# stoichea_v0_1.net
KiCad netlist of a schematic drawn in EAGLE
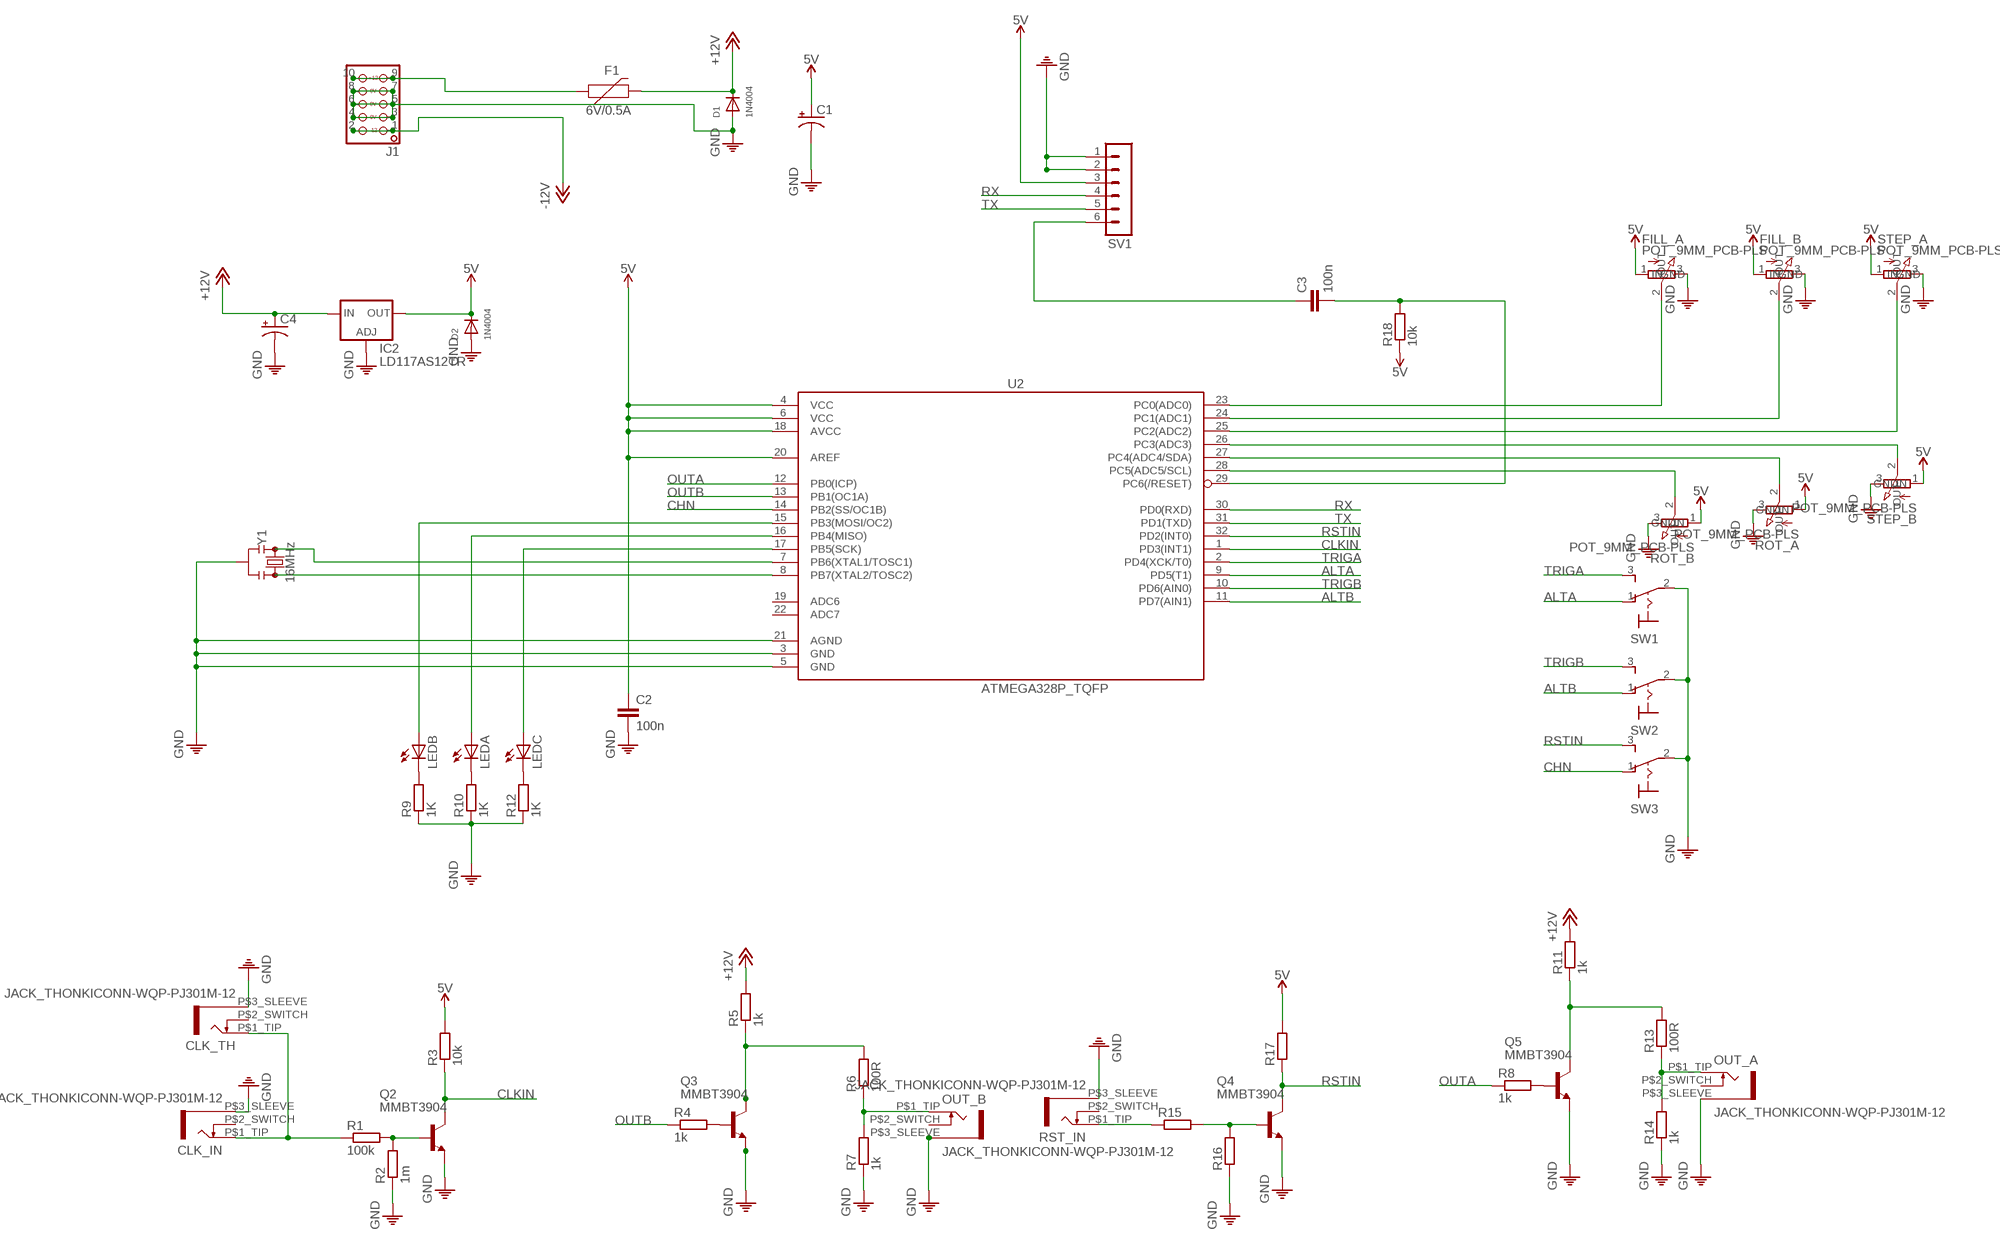
[diagram p0: schematic, sheet 1]

(export (version "E")
  (design (tool "Eeschema 10.0.6"))
  (components
    (comp (ref "C1")
      (value "CAPACITOR_POLARIZED-USE2.5-5")
      (footprint "eagle-import:E2,5-5")
      (libsource (lib "eagle-import") (part "CAPACITOR_POLARIZED-USE2.5-5"))
    )
    (comp (ref "C2")
      (value "100n")
      (footprint "eagle-import:C0603K")
      (libsource (lib "eagle-import") (part "CAPACITOR-EUC0603K"))
    )
    (comp (ref "C3")
      (value "100n")
      (footprint "eagle-import:C0603K")
      (libsource (lib "eagle-import") (part "CAPACITOR-EUC0603K"))
    )
    (comp (ref "C4")
      (value "CAPACITOR_POLARIZED-USE2.5-5")
      (footprint "eagle-import:E2,5-5")
      (libsource (lib "eagle-import") (part "CAPACITOR_POLARIZED-USE2.5-5"))
    )
    (comp (ref "CLK_IN")
      (value "JACK_THONKICONN-WQP-PJ301M-12")
      (footprint "eagle-import:WQP-PJ301M-12_JACK")
      (libsource (lib "eagle-import") (part "JACK_THONKICONN-WQP-PJ301M-12"))
    )
    (comp (ref "CLK_TH")
      (value "JACK_THONKICONN-WQP-PJ301M-12")
      (footprint "eagle-import:WQP-PJ301M-12_JACK")
      (libsource (lib "eagle-import") (part "JACK_THONKICONN-WQP-PJ301M-12"))
    )
    (comp (ref "D1")
      (value "1N4004")
      (footprint "eagle-import:SOD-323F")
      (libsource (lib "eagle-import") (part "DIODESOD-323F"))
    )
    (comp (ref "D2")
      (value "1N4004")
      (footprint "eagle-import:SOD-323F")
      (libsource (lib "eagle-import") (part "DIODESOD-323F"))
    )
    (comp (ref "F1")
      (value "6V/0.5A")
      (footprint "eagle-import:1206")
      (libsource (lib "eagle-import") (part "FUSE-PPTC_HALF-AMP"))
    )
    (comp (ref "FILL_A")
      (value "POT_9MM_PCB-PLS")
      (footprint "eagle-import:9MM_PLS")
      (libsource (lib "eagle-import") (part "POT_9MM_PCB-PLS"))
    )
    (comp (ref "FILL_B")
      (value "POT_9MM_PCB-PLS")
      (footprint "eagle-import:9MM_PLS")
      (libsource (lib "eagle-import") (part "POT_9MM_PCB-PLS"))
    )
    (comp (ref "IC2")
      (value "LD117AS12TR")
      (footprint "eagle-import:SOT223")
      (libsource (lib "eagle-import") (part "LD117A?S12TR"))
    )
    (comp (ref "J1")
      (value "HEADER-EUROPWR_2X05-OPEN")
      (footprint "eagle-import:2X05_EUROPWR_OPEN")
      (libsource (lib "eagle-import") (part "HEADER-EUROPWR_2X05-OPEN"))
    )
    (comp (ref "LEDA")
      (value "LED3MM")
      (footprint "eagle-import:LED3MM")
      (libsource (lib "eagle-import") (part "LED3MM"))
    )
    (comp (ref "LEDB")
      (value "LED3MM")
      (footprint "eagle-import:LED3MM")
      (libsource (lib "eagle-import") (part "LED3MM"))
    )
    (comp (ref "LEDC")
      (value "LED3MM")
      (footprint "eagle-import:LED3MM")
      (libsource (lib "eagle-import") (part "LED3MM"))
    )
    (comp (ref "OUT_A")
      (value "JACK_THONKICONN-WQP-PJ301M-12")
      (footprint "eagle-import:WQP-PJ301M-12_JACK")
      (libsource (lib "eagle-import") (part "JACK_THONKICONN-WQP-PJ301M-12"))
    )
    (comp (ref "OUT_B")
      (value "JACK_THONKICONN-WQP-PJ301M-12")
      (footprint "eagle-import:WQP-PJ301M-12_JACK")
      (libsource (lib "eagle-import") (part "JACK_THONKICONN-WQP-PJ301M-12"))
    )
    (comp (ref "Q2")
      (value "MMBT3904")
      (footprint "eagle-import:SOT23-BEC")
      (libsource (lib "eagle-import") (part "TRANSISTOR-NPN-SOT23-BECMMBT3904LT1"))
    )
    (comp (ref "Q3")
      (value "MMBT3904")
      (footprint "eagle-import:SOT23-BEC")
      (libsource (lib "eagle-import") (part "TRANSISTOR-NPN-SOT23-BECMMBT3904LT1"))
    )
    (comp (ref "Q4")
      (value "MMBT3904")
      (footprint "eagle-import:SOT23-BEC")
      (libsource (lib "eagle-import") (part "TRANSISTOR-NPN-SOT23-BECMMBT3904LT1"))
    )
    (comp (ref "Q5")
      (value "MMBT3904")
      (footprint "eagle-import:SOT23-BEC")
      (libsource (lib "eagle-import") (part "TRANSISTOR-NPN-SOT23-BECMMBT3904LT1"))
    )
    (comp (ref "R1")
      (value "100k")
      (footprint "eagle-import:R0603")
      (libsource (lib "eagle-import") (part "RESISTOR-EU_R0603"))
    )
    (comp (ref "R2")
      (value "1m")
      (footprint "eagle-import:R0603")
      (libsource (lib "eagle-import") (part "RESISTOR-EU_R0603"))
    )
    (comp (ref "R3")
      (value "10k")
      (footprint "eagle-import:R0603")
      (libsource (lib "eagle-import") (part "RESISTOR-EU_R0603"))
    )
    (comp (ref "R4")
      (value "1k")
      (footprint "eagle-import:R0603")
      (libsource (lib "eagle-import") (part "RESISTOR-EU_R0603"))
    )
    (comp (ref "R5")
      (value "1k")
      (footprint "eagle-import:R0603")
      (libsource (lib "eagle-import") (part "RESISTOR-EU_R0603"))
    )
    (comp (ref "R6")
      (value "100R")
      (footprint "eagle-import:R0603")
      (libsource (lib "eagle-import") (part "RESISTOR-EU_R0603"))
    )
    (comp (ref "R7")
      (value "1k")
      (footprint "eagle-import:R0603")
      (libsource (lib "eagle-import") (part "RESISTOR-EU_R0603"))
    )
    (comp (ref "R8")
      (value "1k")
      (footprint "eagle-import:R0603")
      (libsource (lib "eagle-import") (part "RESISTOR-EU_R0603"))
    )
    (comp (ref "R9")
      (value "1K")
      (footprint "eagle-import:R0603")
      (libsource (lib "eagle-import") (part "RESISTOR-EU_R0603"))
    )
    (comp (ref "R10")
      (value "1K")
      (footprint "eagle-import:R0603")
      (libsource (lib "eagle-import") (part "RESISTOR-EU_R0603"))
    )
    (comp (ref "R11")
      (value "1k")
      (footprint "eagle-import:R0603")
      (libsource (lib "eagle-import") (part "RESISTOR-EU_R0603"))
    )
    (comp (ref "R12")
      (value "1K")
      (footprint "eagle-import:R0603")
      (libsource (lib "eagle-import") (part "RESISTOR-EU_R0603"))
    )
    (comp (ref "R13")
      (value "100R")
      (footprint "eagle-import:R0603")
      (libsource (lib "eagle-import") (part "RESISTOR-EU_R0603"))
    )
    (comp (ref "R14")
      (value "1k")
      (footprint "eagle-import:R0603")
      (libsource (lib "eagle-import") (part "RESISTOR-EU_R0603"))
    )
    (comp (ref "R15")
      (value "RESISTOR-EU_R0603")
      (footprint "eagle-import:R0603")
      (libsource (lib "eagle-import") (part "RESISTOR-EU_R0603"))
    )
    (comp (ref "R16")
      (value "RESISTOR-EU_R0603")
      (footprint "eagle-import:R0603")
      (libsource (lib "eagle-import") (part "RESISTOR-EU_R0603"))
    )
    (comp (ref "R17")
      (value "RESISTOR-EU_R0603")
      (footprint "eagle-import:R0603")
      (libsource (lib "eagle-import") (part "RESISTOR-EU_R0603"))
    )
    (comp (ref "R18")
      (value "10k")
      (footprint "eagle-import:R0603")
      (libsource (lib "eagle-import") (part "RESISTOR-EU_R0603"))
    )
    (comp (ref "ROT_A")
      (value "POT_9MM_PCB-PLS")
      (footprint "eagle-import:9MM_PLS")
      (libsource (lib "eagle-import") (part "POT_9MM_PCB-PLS"))
    )
    (comp (ref "ROT_B")
      (value "POT_9MM_PCB-PLS")
      (footprint "eagle-import:9MM_PLS")
      (libsource (lib "eagle-import") (part "POT_9MM_PCB-PLS"))
    )
    (comp (ref "RST_IN")
      (value "JACK_THONKICONN-WQP-PJ301M-12")
      (footprint "eagle-import:WQP-PJ301M-12_JACK")
      (libsource (lib "eagle-import") (part "JACK_THONKICONN-WQP-PJ301M-12"))
    )
    (comp (ref "STEP_A")
      (value "POT_9MM_PCB-PLS")
      (footprint "eagle-import:9MM_PLS")
      (libsource (lib "eagle-import") (part "POT_9MM_PCB-PLS"))
    )
    (comp (ref "STEP_B")
      (value "POT_9MM_PCB-PLS")
      (footprint "eagle-import:9MM_PLS")
      (libsource (lib "eagle-import") (part "POT_9MM_PCB-PLS"))
    )
    (comp (ref "SV1")
      (value "MA06-1")
      (footprint "eagle-import:MA06-1")
      (libsource (lib "eagle-import") (part "MA06-1"))
    )
    (comp (ref "SW1")
      (value "SWITCH-SPDT-320-916")
      (footprint "eagle-import:320-916")
      (libsource (lib "eagle-import") (part "SWITCH-SPDT-320-916"))
    )
    (comp (ref "SW2")
      (value "SWITCH-SPDT-320-916")
      (footprint "eagle-import:320-916")
      (libsource (lib "eagle-import") (part "SWITCH-SPDT-320-916"))
    )
    (comp (ref "SW3")
      (value "SWITCH-SPDT-320-916")
      (footprint "eagle-import:320-916")
      (libsource (lib "eagle-import") (part "SWITCH-SPDT-320-916"))
    )
    (comp (ref "U2")
      (value "ATMEGA328P_TQFP")
      (footprint "eagle-import:TQFP32-08")
      (libsource (lib "eagle-import") (part "ATMEGA328P_TQFP"))
    )
    (comp (ref "Y1")
      (value "16MHz")
      (footprint "eagle-import:RESONATOR-SMD-3.2X1.3")
      (libsource (lib "eagle-import") (part "RESONATORSMD-3.2X1.3"))
    )
  )
  (nets
    (net (code "1") (name "+12V") (class "Default")
      (node (ref "C4") (pin "+") (pinfunction "+_+") (pintype "passive"))
      (node (ref "D1") (pin "C") (pinfunction "C_C") (pintype "passive"))
      (node (ref "F1") (pin "2") (pinfunction "2_2") (pintype "bidirectional"))
      (node (ref "IC2") (pin "3") (pinfunction "IN_3") (pintype "input"))
      (node (ref "R11") (pin "2") (pinfunction "2_2") (pintype "passive"))
      (node (ref "R5") (pin "2") (pinfunction "2_2") (pintype "passive"))
    )
    (net (code "2") (name "-12V") (class "Default")
      (node (ref "J1") (pin "1") (pinfunction "1_1") (pintype "passive"))
      (node (ref "J1") (pin "2") (pinfunction "2_2") (pintype "passive"))
    )
    (net (code "3") (name "/ALTA") (class "Default")
      (node (ref "SW1") (pin "1") (pinfunction "O_1") (pintype "passive"))
      (node (ref "U2") (pin "9") (pinfunction "PD5(T1)_9") (pintype "bidirectional"))
    )
    (net (code "4") (name "/ALTB") (class "Default")
      (node (ref "SW2") (pin "1") (pinfunction "O_1") (pintype "passive"))
      (node (ref "U2") (pin "11") (pinfunction "PD7(AIN1)_11") (pintype "bidirectional"))
    )
    (net (code "5") (name "/CHN") (class "Default")
      (node (ref "SW3") (pin "1") (pinfunction "O_1") (pintype "passive"))
      (node (ref "U2") (pin "14") (pinfunction "PB2(SS/OC1B)_14") (pintype "bidirectional"))
    )
    (net (code "6") (name "/CLKIN") (class "Default")
      (node (ref "Q2") (pin "C") (pinfunction "C_C") (pintype "passive"))
      (node (ref "R3") (pin "1") (pinfunction "1_1") (pintype "passive"))
      (node (ref "U2") (pin "1") (pinfunction "PD3(INT1)_1") (pintype "bidirectional"))
    )
    (net (code "7") (name "/OUTA") (class "Default")
      (node (ref "R8") (pin "1") (pinfunction "1_1") (pintype "passive"))
      (node (ref "U2") (pin "12") (pinfunction "PB0(ICP)_12") (pintype "bidirectional"))
    )
    (net (code "8") (name "/OUTB") (class "Default")
      (node (ref "R4") (pin "1") (pinfunction "1_1") (pintype "passive"))
      (node (ref "U2") (pin "13") (pinfunction "PB1(OC1A)_13") (pintype "bidirectional"))
    )
    (net (code "9") (name "/RSTIN") (class "Default")
      (node (ref "Q4") (pin "C") (pinfunction "C_C") (pintype "passive"))
      (node (ref "R17") (pin "1") (pinfunction "1_1") (pintype "passive"))
      (node (ref "SW3") (pin "3") (pinfunction "S_3") (pintype "passive"))
      (node (ref "U2") (pin "32") (pinfunction "PD2(INT0)_32") (pintype "bidirectional"))
    )
    (net (code "10") (name "/RX") (class "Default")
      (node (ref "SV1") (pin "4") (pinfunction "4_4") (pintype "passive"))
      (node (ref "U2") (pin "30") (pinfunction "PD0(RXD)_30") (pintype "bidirectional"))
    )
    (net (code "11") (name "/TRIGA") (class "Default")
      (node (ref "SW1") (pin "3") (pinfunction "S_3") (pintype "passive"))
      (node (ref "U2") (pin "2") (pinfunction "PD4(XCK/T0)_2") (pintype "bidirectional"))
    )
    (net (code "12") (name "/TRIGB") (class "Default")
      (node (ref "SW2") (pin "3") (pinfunction "S_3") (pintype "passive"))
      (node (ref "U2") (pin "10") (pinfunction "PD6(AIN0)_10") (pintype "bidirectional"))
    )
    (net (code "13") (name "/TX") (class "Default")
      (node (ref "SV1") (pin "5") (pinfunction "5_5") (pintype "passive"))
      (node (ref "U2") (pin "31") (pinfunction "PD1(TXD)_31") (pintype "bidirectional"))
    )
    (net (code "14") (name "5V") (class "Default")
      (node (ref "C1") (pin "+") (pinfunction "+_+") (pintype "passive"))
      (node (ref "C2") (pin "1") (pinfunction "1_1") (pintype "passive"))
      (node (ref "D2") (pin "C") (pinfunction "C_C") (pintype "passive"))
      (node (ref "FILL_A") (pin "1") (pinfunction "GND_1") (pintype "passive"))
      (node (ref "FILL_B") (pin "1") (pinfunction "GND_1") (pintype "passive"))
      (node (ref "IC2") (pin "4") (pinfunction "OUT_4") (pintype "passive"))
      (node (ref "R17") (pin "2") (pinfunction "2_2") (pintype "passive"))
      (node (ref "R18") (pin "1") (pinfunction "1_1") (pintype "passive"))
      (node (ref "R3") (pin "2") (pinfunction "2_2") (pintype "passive"))
      (node (ref "ROT_A") (pin "1") (pinfunction "GND_1") (pintype "passive"))
      (node (ref "ROT_B") (pin "1") (pinfunction "GND_1") (pintype "passive"))
      (node (ref "STEP_A") (pin "1") (pinfunction "GND_1") (pintype "passive"))
      (node (ref "STEP_B") (pin "1") (pinfunction "GND_1") (pintype "passive"))
      (node (ref "SV1") (pin "3") (pinfunction "3_3") (pintype "passive"))
      (node (ref "U2") (pin "18") (pinfunction "AVCC_18") (pintype "bidirectional"))
      (node (ref "U2") (pin "20") (pinfunction "AREF_20") (pintype "bidirectional"))
      (node (ref "U2") (pin "4") (pinfunction "VCC_4") (pintype "bidirectional"))
      (node (ref "U2") (pin "6") (pinfunction "VCC_6") (pintype "bidirectional"))
    )
    (net (code "15") (name "GND") (class "Default")
      (node (ref "C1") (pin "-") (pinfunction "-_-") (pintype "passive"))
      (node (ref "C2") (pin "2") (pinfunction "2_2") (pintype "passive"))
      (node (ref "C4") (pin "-") (pinfunction "-_-") (pintype "passive"))
      (node (ref "CLK_IN") (pin "P$3_SLEEVE") (pinfunction "1_P$3_SLEEVE") (pintype "passive"))
      (node (ref "CLK_TH") (pin "P$3_SLEEVE") (pinfunction "1_P$3_SLEEVE") (pintype "passive"))
      (node (ref "D1") (pin "A") (pinfunction "A_A") (pintype "passive"))
      (node (ref "D2") (pin "A") (pinfunction "A_A") (pintype "passive"))
      (node (ref "FILL_A") (pin "3") (pinfunction "IN_3") (pintype "passive"))
      (node (ref "FILL_B") (pin "3") (pinfunction "IN_3") (pintype "passive"))
      (node (ref "IC2") (pin "1") (pinfunction "ADJ_1") (pintype "input"))
      (node (ref "J1") (pin "3") (pinfunction "3_3") (pintype "passive"))
      (node (ref "J1") (pin "4") (pinfunction "4_4") (pintype "passive"))
      (node (ref "J1") (pin "5") (pinfunction "5_5") (pintype "passive"))
      (node (ref "J1") (pin "6") (pinfunction "6_6") (pintype "passive"))
      (node (ref "J1") (pin "7") (pinfunction "7_7") (pintype "passive"))
      (node (ref "J1") (pin "8") (pinfunction "8_8") (pintype "passive"))
      (node (ref "OUT_A") (pin "P$3_SLEEVE") (pinfunction "1_P$3_SLEEVE") (pintype "passive"))
      (node (ref "OUT_B") (pin "P$3_SLEEVE") (pinfunction "1_P$3_SLEEVE") (pintype "passive"))
      (node (ref "Q2") (pin "E") (pinfunction "E_E") (pintype "passive"))
      (node (ref "Q3") (pin "E") (pinfunction "E_E") (pintype "passive"))
      (node (ref "Q4") (pin "E") (pinfunction "E_E") (pintype "passive"))
      (node (ref "Q5") (pin "E") (pinfunction "E_E") (pintype "passive"))
      (node (ref "R10") (pin "1") (pinfunction "1_1") (pintype "passive"))
      (node (ref "R12") (pin "1") (pinfunction "1_1") (pintype "passive"))
      (node (ref "R14") (pin "1") (pinfunction "1_1") (pintype "passive"))
      (node (ref "R16") (pin "1") (pinfunction "1_1") (pintype "passive"))
      (node (ref "R2") (pin "1") (pinfunction "1_1") (pintype "passive"))
      (node (ref "R7") (pin "1") (pinfunction "1_1") (pintype "passive"))
      (node (ref "R9") (pin "1") (pinfunction "1_1") (pintype "passive"))
      (node (ref "ROT_A") (pin "3") (pinfunction "IN_3") (pintype "passive"))
      (node (ref "ROT_B") (pin "3") (pinfunction "IN_3") (pintype "passive"))
      (node (ref "RST_IN") (pin "P$3_SLEEVE") (pinfunction "1_P$3_SLEEVE") (pintype "passive"))
      (node (ref "STEP_A") (pin "3") (pinfunction "IN_3") (pintype "passive"))
      (node (ref "STEP_B") (pin "3") (pinfunction "IN_3") (pintype "passive"))
      (node (ref "SV1") (pin "1") (pinfunction "1_1") (pintype "passive"))
      (node (ref "SV1") (pin "2") (pinfunction "2_2") (pintype "passive"))
      (node (ref "SW1") (pin "2") (pinfunction "P_2") (pintype "passive"))
      (node (ref "SW2") (pin "2") (pinfunction "P_2") (pintype "passive"))
      (node (ref "SW3") (pin "2") (pinfunction "P_2") (pintype "passive"))
      (node (ref "U2") (pin "21") (pinfunction "AGND_21") (pintype "bidirectional"))
      (node (ref "U2") (pin "3") (pinfunction "GND_3") (pintype "bidirectional"))
      (node (ref "U2") (pin "5") (pinfunction "GND_5") (pintype "bidirectional"))
      (node (ref "Y1") (pin "2") (pinfunction "2_2") (pintype "passive"))
    )
    (net (code "16") (name "Net-(C3-Pad1)") (class "Default")
      (node (ref "C3") (pin "1") (pinfunction "1_1") (pintype "passive"))
      (node (ref "SV1") (pin "6") (pinfunction "6_6") (pintype "passive"))
    )
    (net (code "17") (name "Net-(CLK_IN-2)") (class "Default")
      (node (ref "CLK_IN") (pin "P$1_TIP") (pinfunction "2_P$1_TIP") (pintype "passive"))
      (node (ref "CLK_TH") (pin "P$1_TIP") (pinfunction "2_P$1_TIP") (pintype "passive"))
      (node (ref "R1") (pin "1") (pinfunction "1_1") (pintype "passive"))
    )
    (net (code "18") (name "Net-(F1-Pad1)") (class "Default")
      (node (ref "F1") (pin "1") (pinfunction "1_1") (pintype "bidirectional"))
      (node (ref "J1") (pin "10") (pinfunction "10_10") (pintype "passive"))
      (node (ref "J1") (pin "9") (pinfunction "9_9") (pintype "passive"))
    )
    (net (code "19") (name "Net-(FILL_A-OUT)") (class "Default")
      (node (ref "FILL_A") (pin "2") (pinfunction "OUT_2") (pintype "passive"))
      (node (ref "U2") (pin "23") (pinfunction "PC0(ADC0)_23") (pintype "bidirectional"))
    )
    (net (code "20") (name "Net-(FILL_B-OUT)") (class "Default")
      (node (ref "FILL_B") (pin "2") (pinfunction "OUT_2") (pintype "passive"))
      (node (ref "U2") (pin "24") (pinfunction "PC1(ADC1)_24") (pintype "bidirectional"))
    )
    (net (code "21") (name "Net-(LEDA-C)") (class "Default")
      (node (ref "LEDA") (pin "K") (pinfunction "C_K") (pintype "passive"))
      (node (ref "R10") (pin "2") (pinfunction "2_2") (pintype "passive"))
    )
    (net (code "22") (name "Net-(LEDB-C)") (class "Default")
      (node (ref "LEDB") (pin "K") (pinfunction "C_K") (pintype "passive"))
      (node (ref "R9") (pin "2") (pinfunction "2_2") (pintype "passive"))
    )
    (net (code "23") (name "Net-(LEDC-C)") (class "Default")
      (node (ref "LEDC") (pin "K") (pinfunction "C_K") (pintype "passive"))
      (node (ref "R12") (pin "2") (pinfunction "2_2") (pintype "passive"))
    )
    (net (code "24") (name "Net-(OUT_A-2)") (class "Default")
      (node (ref "OUT_A") (pin "P$1_TIP") (pinfunction "2_P$1_TIP") (pintype "passive"))
      (node (ref "R13") (pin "1") (pinfunction "1_1") (pintype "passive"))
      (node (ref "R14") (pin "2") (pinfunction "2_2") (pintype "passive"))
    )
    (net (code "25") (name "Net-(OUT_B-2)") (class "Default")
      (node (ref "OUT_B") (pin "P$1_TIP") (pinfunction "2_P$1_TIP") (pintype "passive"))
      (node (ref "R6") (pin "1") (pinfunction "1_1") (pintype "passive"))
      (node (ref "R7") (pin "2") (pinfunction "2_2") (pintype "passive"))
    )
    (net (code "26") (name "Net-(Q2-PadB)") (class "Default")
      (node (ref "Q2") (pin "B") (pinfunction "B_B") (pintype "passive"))
      (node (ref "R1") (pin "2") (pinfunction "2_2") (pintype "passive"))
      (node (ref "R2") (pin "2") (pinfunction "2_2") (pintype "passive"))
    )
    (net (code "27") (name "Net-(Q3-PadB)") (class "Default")
      (node (ref "Q3") (pin "B") (pinfunction "B_B") (pintype "passive"))
      (node (ref "R4") (pin "2") (pinfunction "2_2") (pintype "passive"))
    )
    (net (code "28") (name "Net-(Q3-PadC)") (class "Default")
      (node (ref "Q3") (pin "C") (pinfunction "C_C") (pintype "passive"))
      (node (ref "R5") (pin "1") (pinfunction "1_1") (pintype "passive"))
      (node (ref "R6") (pin "2") (pinfunction "2_2") (pintype "passive"))
    )
    (net (code "29") (name "Net-(Q4-PadB)") (class "Default")
      (node (ref "Q4") (pin "B") (pinfunction "B_B") (pintype "passive"))
      (node (ref "R15") (pin "2") (pinfunction "2_2") (pintype "passive"))
      (node (ref "R16") (pin "2") (pinfunction "2_2") (pintype "passive"))
    )
    (net (code "30") (name "Net-(Q5-PadB)") (class "Default")
      (node (ref "Q5") (pin "B") (pinfunction "B_B") (pintype "passive"))
      (node (ref "R8") (pin "2") (pinfunction "2_2") (pintype "passive"))
    )
    (net (code "31") (name "Net-(Q5-PadC)") (class "Default")
      (node (ref "Q5") (pin "C") (pinfunction "C_C") (pintype "passive"))
      (node (ref "R11") (pin "1") (pinfunction "1_1") (pintype "passive"))
      (node (ref "R13") (pin "2") (pinfunction "2_2") (pintype "passive"))
    )
    (net (code "32") (name "Net-(ROT_A-OUT)") (class "Default")
      (node (ref "ROT_A") (pin "2") (pinfunction "OUT_2") (pintype "passive"))
      (node (ref "U2") (pin "27") (pinfunction "PC4(ADC4/SDA)_27") (pintype "bidirectional"))
    )
    (net (code "33") (name "Net-(ROT_B-OUT)") (class "Default")
      (node (ref "ROT_B") (pin "2") (pinfunction "OUT_2") (pintype "passive"))
      (node (ref "U2") (pin "28") (pinfunction "PC5(ADC5/SCL)_28") (pintype "bidirectional"))
    )
    (net (code "34") (name "Net-(RST_IN-2)") (class "Default")
      (node (ref "R15") (pin "1") (pinfunction "1_1") (pintype "passive"))
      (node (ref "RST_IN") (pin "P$1_TIP") (pinfunction "2_P$1_TIP") (pintype "passive"))
    )
    (net (code "35") (name "Net-(STEP_A-OUT)") (class "Default")
      (node (ref "STEP_A") (pin "2") (pinfunction "OUT_2") (pintype "passive"))
      (node (ref "U2") (pin "25") (pinfunction "PC2(ADC2)_25") (pintype "bidirectional"))
    )
    (net (code "36") (name "Net-(STEP_B-OUT)") (class "Default")
      (node (ref "STEP_B") (pin "2") (pinfunction "OUT_2") (pintype "passive"))
      (node (ref "U2") (pin "26") (pinfunction "PC3(ADC3)_26") (pintype "bidirectional"))
    )
    (net (code "37") (name "Net-(U2-PB3(MOSI{slash}OC2))") (class "Default")
      (node (ref "LEDB") (pin "A") (pinfunction "A_A") (pintype "passive"))
      (node (ref "U2") (pin "15") (pinfunction "PB3(MOSI/OC2)_15") (pintype "bidirectional"))
    )
    (net (code "38") (name "Net-(U2-PB4(MISO))") (class "Default")
      (node (ref "LEDA") (pin "A") (pinfunction "A_A") (pintype "passive"))
      (node (ref "U2") (pin "16") (pinfunction "PB4(MISO)_16") (pintype "bidirectional"))
    )
    (net (code "39") (name "Net-(U2-PB5(SCK))") (class "Default")
      (node (ref "LEDC") (pin "A") (pinfunction "A_A") (pintype "passive"))
      (node (ref "U2") (pin "17") (pinfunction "PB5(SCK)_17") (pintype "bidirectional"))
    )
    (net (code "40") (name "Net-(U2-PB6(XTAL1{slash}TOSC1))") (class "Default")
      (node (ref "U2") (pin "7") (pinfunction "PB6(XTAL1/TOSC1)_7") (pintype "bidirectional"))
      (node (ref "Y1") (pin "1") (pinfunction "1_1") (pintype "passive"))
    )
    (net (code "41") (name "Net-(U2-PB7(XTAL2{slash}TOSC2))") (class "Default")
      (node (ref "U2") (pin "8") (pinfunction "PB7(XTAL2/TOSC2)_8") (pintype "bidirectional"))
      (node (ref "Y1") (pin "3") (pinfunction "3_3") (pintype "passive"))
    )
    (net (code "42") (name "Net-(U2-PC6({slash}RESET))") (class "Default")
      (node (ref "C3") (pin "2") (pinfunction "2_2") (pintype "passive"))
      (node (ref "R18") (pin "2") (pinfunction "2_2") (pintype "passive"))
      (node (ref "U2") (pin "29") (pinfunction "PC6(/RESET)_29") (pintype "bidirectional"))
    )
    (net (code "43") (name "unconnected-(CLK_IN-3-PadP$2_SWITCH)") (class "Default")
      (node (ref "CLK_IN") (pin "P$2_SWITCH") (pinfunction "3_P$2_SWITCH") (pintype "passive"))
    )
    (net (code "44") (name "unconnected-(CLK_TH-3-PadP$2_SWITCH)") (class "Default")
      (node (ref "CLK_TH") (pin "P$2_SWITCH") (pinfunction "3_P$2_SWITCH") (pintype "passive"))
    )
    (net (code "45") (name "unconnected-(OUT_A-3-PadP$2_SWITCH)") (class "Default")
      (node (ref "OUT_A") (pin "P$2_SWITCH") (pinfunction "3_P$2_SWITCH") (pintype "passive"))
    )
    (net (code "46") (name "unconnected-(OUT_B-3-PadP$2_SWITCH)") (class "Default")
      (node (ref "OUT_B") (pin "P$2_SWITCH") (pinfunction "3_P$2_SWITCH") (pintype "passive"))
    )
    (net (code "47") (name "unconnected-(RST_IN-3-PadP$2_SWITCH)") (class "Default")
      (node (ref "RST_IN") (pin "P$2_SWITCH") (pinfunction "3_P$2_SWITCH") (pintype "passive"))
    )
    (net (code "48") (name "unconnected-(U2-ADC6-Pad19)") (class "Default")
      (node (ref "U2") (pin "19") (pinfunction "ADC6_19") (pintype "bidirectional"))
    )
    (net (code "49") (name "unconnected-(U2-ADC7-Pad22)") (class "Default")
      (node (ref "U2") (pin "22") (pinfunction "ADC7_22") (pintype "bidirectional"))
    )
  )
)
